# 10_CAN_Interface.net
KiCad netlist of a schematic drawn in Altium Designer
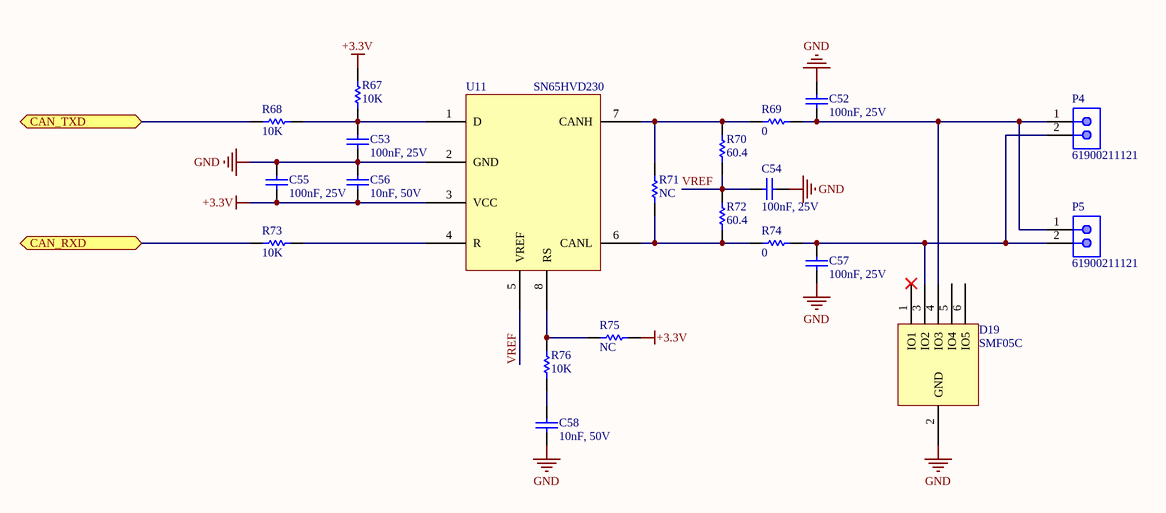
[diagram p0: 10_CAN_Interface.SchDoc]

(export (version "E")
  (design (tool "Eeschema 10.0.6"))
  (components
    (comp (ref "C52")
      (value "100nF, 25V")
      (footprint "WCAP-CSGP_0603_H=0.8mm_Reflow")
      (description "WCAP-CSGP Multilayer Ceramic Chip Capacitor, General Purpose, size 0603, X7R, 100nF, 25V")
      (fields
        (field (name "MANUFACTURER PART NUMBER") "885012206071")
        (field (name "MANUFACTURER") "Wurth Elektronik")
      )
      (libsource (lib "Altium_WCAP-CSGP (rev20a)") (part "885012206071"))
    )
    (comp (ref "C53")
      (value "100nF, 25V")
      (footprint "WCAP-CSGP_0603_H=0.8mm_Reflow")
      (description "WCAP-CSGP Multilayer Ceramic Chip Capacitor, General Purpose, size 0603, X7R, 100nF, 25V")
      (fields
        (field (name "MANUFACTURER PART NUMBER") "885012206071")
        (field (name "MANUFACTURER") "Wurth Elektronik")
      )
      (libsource (lib "Altium_WCAP-CSGP (rev20a)") (part "885012206071"))
    )
    (comp (ref "C54")
      (value "100nF, 25V")
      (footprint "WCAP-CSGP_0603_H=0.8mm_Reflow")
      (description "WCAP-CSGP Multilayer Ceramic Chip Capacitor, General Purpose, size 0603, X7R, 100nF, 25V")
      (fields
        (field (name "MANUFACTURER PART NUMBER") "885012206071")
        (field (name "MANUFACTURER") "Wurth Elektronik")
      )
      (libsource (lib "Altium_WCAP-CSGP (rev20a)") (part "885012206071"))
    )
    (comp (ref "C55")
      (value "100nF, 25V")
      (footprint "WCAP-CSGP_0603_H=0.8mm_Reflow")
      (description "WCAP-CSGP Multilayer Ceramic Chip Capacitor, General Purpose, size 0603, X7R, 100nF, 25V")
      (fields
        (field (name "MANUFACTURER PART NUMBER") "885012206071")
        (field (name "MANUFACTURER") "Wurth Elektronik")
      )
      (libsource (lib "Altium_WCAP-CSGP (rev20a)") (part "885012206071"))
    )
    (comp (ref "C56")
      (value "10nF, 50V")
      (footprint "WCAP-CSGP_0603_H=0.8mm_Reflow")
      (description "WCAP-CSGP Multilayer Ceramic Chip Capacitor, General Purpose, size 0603, X7R, 10nF, 50V")
      (fields
        (field (name "MANUFACTURER PART NUMBER") "885012206089")
        (field (name "MANUFACTURER") "Wurth Elektronik")
      )
      (libsource (lib "Altium_WCAP-CSGP (rev20a)") (part "885012206089"))
    )
    (comp (ref "C57")
      (value "100nF, 25V")
      (footprint "WCAP-CSGP_0603_H=0.8mm_Reflow")
      (description "WCAP-CSGP Multilayer Ceramic Chip Capacitor, General Purpose, size 0603, X7R, 100nF, 25V")
      (fields
        (field (name "MANUFACTURER PART NUMBER") "885012206071")
        (field (name "MANUFACTURER") "Wurth Elektronik")
      )
      (libsource (lib "Altium_WCAP-CSGP (rev20a)") (part "885012206071"))
    )
    (comp (ref "C58")
      (value "10nF, 50V")
      (footprint "WCAP-CSGP_0603_H=0.8mm_Reflow")
      (description "WCAP-CSGP Multilayer Ceramic Chip Capacitor, General Purpose, size 0603, X7R, 10nF, 50V")
      (fields
        (field (name "MANUFACTURER PART NUMBER") "885012206089")
        (field (name "MANUFACTURER") "Wurth Elektronik")
      )
      (libsource (lib "Altium_WCAP-CSGP (rev20a)") (part "885012206089"))
    )
    (comp (ref "D19")
      (value "SMF05C")
      (footprint "SOT65P210X110-6N")
      (libsource (lib "MiclsLib") (part "SMF05C"))
    )
    (comp (ref "P4")
      (value "61900211121")
      (footprint "61900211121")
      (description "WR-WTB THT Male Vertical Locking Header, pitch 2.54mm, 2p")
      (fields (field (name "PUBLISHER") "Wurth Elektronik"))
      (libsource (lib "653008114822_Altium_WR-WTB_rev20a") (part "61900211121"))
    )
    (comp (ref "P5")
      (value "61900211121")
      (footprint "61900211121")
      (description "WR-WTB THT Male Vertical Locking Header, pitch 2.54mm, 2p")
      (fields (field (name "PUBLISHER") "Wurth Elektronik"))
      (libsource (lib "653008114822_Altium_WR-WTB_rev20a") (part "61900211121"))
    )
    (comp (ref "R67")
      (value "10K")
      (footprint "RES-SM-0603")
      (description "Resistor")
      (fields (field (name "Comment") "RESISTOR SMD"))
      (libsource (lib "PIF_Library") (part "RESISTOR SMD"))
    )
    (comp (ref "R68")
      (value "10K")
      (footprint "RES-SM-0603")
      (description "Resistor")
      (fields (field (name "Comment") "RESISTOR SMD"))
      (libsource (lib "PIF_Library") (part "RESISTOR SMD"))
    )
    (comp (ref "R69")
      (value "0")
      (footprint "RES-SM-0603")
      (description "Resistor")
      (fields (field (name "Comment") "RESISTOR SMD"))
      (libsource (lib "PIF_Library") (part "RESISTOR SMD"))
    )
    (comp (ref "R70")
      (value "60.4")
      (footprint "RES-SM-0603")
      (description "Resistor")
      (fields (field (name "Comment") "RESISTOR SMD"))
      (libsource (lib "PIF_Library") (part "RESISTOR SMD"))
    )
    (comp (ref "R71")
      (value "NC")
      (footprint "RES-SM-0603")
      (description "Resistor")
      (fields (field (name "Comment") "RESISTOR SMD"))
      (libsource (lib "PIF_Library") (part "RESISTOR SMD"))
    )
    (comp (ref "R72")
      (value "60.4")
      (footprint "RES-SM-0603")
      (description "Resistor")
      (fields (field (name "Comment") "RESISTOR SMD"))
      (libsource (lib "PIF_Library") (part "RESISTOR SMD"))
    )
    (comp (ref "R73")
      (value "10K")
      (footprint "RES-SM-0603")
      (description "Resistor")
      (fields (field (name "Comment") "RESISTOR SMD"))
      (libsource (lib "PIF_Library") (part "RESISTOR SMD"))
    )
    (comp (ref "R74")
      (value "0")
      (footprint "RES-SM-0603")
      (description "Resistor")
      (fields (field (name "Comment") "RESISTOR SMD"))
      (libsource (lib "PIF_Library") (part "RESISTOR SMD"))
    )
    (comp (ref "R75")
      (value "NC")
      (footprint "RES-SM-0603")
      (description "Resistor")
      (fields (field (name "Comment") "RESISTOR SMD"))
      (libsource (lib "PIF_Library") (part "RESISTOR SMD"))
    )
    (comp (ref "R76")
      (value "10K")
      (footprint "RES-SM-0603")
      (description "Resistor")
      (fields (field (name "Comment") "RESISTOR SMD"))
      (libsource (lib "PIF_Library") (part "RESISTOR SMD"))
    )
    (comp (ref "U11")
      (value "SN65HVD230")
      (footprint "SOIC127P600X175-8N")
      (libsource (lib "MiclsLib") (part "SN65HVD230"))
    )
  )
  (nets
    (net (code "1") (name "+3.3V") (class "Default")
      (node (ref "C55") (pin "1") (pinfunction "1_1") (pintype "passive"))
      (node (ref "C56") (pin "1") (pinfunction "1_1") (pintype "passive"))
      (node (ref "R67") (pin "2") (pinfunction "2_2") (pintype "passive"))
      (node (ref "R75") (pin "1") (pinfunction "1_1") (pintype "passive"))
      (node (ref "U11") (pin "3") (pinfunction "VCC_3") (pintype "passive"))
    )
    (net (code "2") (name "/CAN_RXD") (class "Default")
      (node (ref "R73") (pin "2") (pinfunction "2_2") (pintype "passive"))
    )
    (net (code "3") (name "/CAN_TXD") (class "Default")
      (node (ref "R68") (pin "2") (pinfunction "2_2") (pintype "passive"))
    )
    (net (code "4") (name "/VREF") (class "Default")
      (node (ref "C54") (pin "2") (pinfunction "2_2") (pintype "passive"))
      (node (ref "R70") (pin "2") (pinfunction "2_2") (pintype "passive"))
      (node (ref "R72") (pin "1") (pinfunction "1_1") (pintype "passive"))
      (node (ref "U11") (pin "5") (pinfunction "VREF_5") (pintype "passive"))
    )
    (net (code "5") (name "GND") (class "Default")
      (node (ref "C52") (pin "2") (pinfunction "2_2") (pintype "passive"))
      (node (ref "C53") (pin "1") (pinfunction "1_1") (pintype "passive"))
      (node (ref "C54") (pin "1") (pinfunction "1_1") (pintype "passive"))
      (node (ref "C55") (pin "2") (pinfunction "2_2") (pintype "passive"))
      (node (ref "C56") (pin "2") (pinfunction "2_2") (pintype "passive"))
      (node (ref "C57") (pin "1") (pinfunction "1_1") (pintype "passive"))
      (node (ref "C58") (pin "1") (pinfunction "1_1") (pintype "passive"))
      (node (ref "D19") (pin "2") (pinfunction "GND_2") (pintype "passive"))
      (node (ref "U11") (pin "2") (pinfunction "GND_2") (pintype "passive"))
    )
    (net (code "6") (name "Net-(C58-Pad2)") (class "Default")
      (node (ref "C58") (pin "2") (pinfunction "2_2") (pintype "passive"))
      (node (ref "R76") (pin "1") (pinfunction "1_1") (pintype "passive"))
    )
    (net (code "7") (name "Net-(D19-IO2)") (class "Default")
      (node (ref "C57") (pin "2") (pinfunction "2_2") (pintype "passive"))
      (node (ref "D19") (pin "3") (pinfunction "IO2_3") (pintype "passive"))
      (node (ref "P4") (pin "2") (pinfunction "2_2") (pintype "passive"))
      (node (ref "P5") (pin "2") (pinfunction "2_2") (pintype "passive"))
      (node (ref "R74") (pin "1") (pinfunction "1_1") (pintype "passive"))
    )
    (net (code "8") (name "Net-(D19-IO3)") (class "Default")
      (node (ref "C52") (pin "1") (pinfunction "1_1") (pintype "passive"))
      (node (ref "D19") (pin "4") (pinfunction "IO3_4") (pintype "passive"))
      (node (ref "P4") (pin "1") (pinfunction "1_1") (pintype "passive"))
      (node (ref "P5") (pin "1") (pinfunction "1_1") (pintype "passive"))
      (node (ref "R69") (pin "1") (pinfunction "1_1") (pintype "passive"))
    )
    (net (code "9") (name "Net-(U11-CANH)") (class "Default")
      (node (ref "R69") (pin "2") (pinfunction "2_2") (pintype "passive"))
      (node (ref "R70") (pin "1") (pinfunction "1_1") (pintype "passive"))
      (node (ref "R71") (pin "1") (pinfunction "1_1") (pintype "passive"))
      (node (ref "U11") (pin "7") (pinfunction "CANH_7") (pintype "passive"))
    )
    (net (code "10") (name "Net-(U11-CANL)") (class "Default")
      (node (ref "R71") (pin "2") (pinfunction "2_2") (pintype "passive"))
      (node (ref "R72") (pin "2") (pinfunction "2_2") (pintype "passive"))
      (node (ref "R74") (pin "2") (pinfunction "2_2") (pintype "passive"))
      (node (ref "U11") (pin "6") (pinfunction "CANL_6") (pintype "passive"))
    )
    (net (code "11") (name "Net-(U11-D)") (class "Default")
      (node (ref "C53") (pin "2") (pinfunction "2_2") (pintype "passive"))
      (node (ref "R67") (pin "1") (pinfunction "1_1") (pintype "passive"))
      (node (ref "R68") (pin "1") (pinfunction "1_1") (pintype "passive"))
      (node (ref "U11") (pin "1") (pinfunction "D_1") (pintype "passive"))
    )
    (net (code "12") (name "Net-(U11-R)") (class "Default")
      (node (ref "R73") (pin "1") (pinfunction "1_1") (pintype "passive"))
      (node (ref "U11") (pin "4") (pinfunction "R_4") (pintype "passive"))
    )
    (net (code "13") (name "Net-(U11-RS)") (class "Default")
      (node (ref "R75") (pin "2") (pinfunction "2_2") (pintype "passive"))
      (node (ref "R76") (pin "2") (pinfunction "2_2") (pintype "passive"))
      (node (ref "U11") (pin "8") (pinfunction "RS_8") (pintype "passive"))
    )
    (net (code "14") (name "unconnected-(D19-IO1-Pad1)") (class "Default")
      (node (ref "D19") (pin "1") (pinfunction "IO1_1") (pintype "passive+no_connect"))
    )
    (net (code "15") (name "unconnected-(D19-IO4-Pad5)") (class "Default")
      (node (ref "D19") (pin "5") (pinfunction "IO4_5") (pintype "passive"))
    )
    (net (code "16") (name "unconnected-(D19-IO5-Pad6)") (class "Default")
      (node (ref "D19") (pin "6") (pinfunction "IO5_6") (pintype "passive"))
    )
  )
)
